# ATOM_-_3x_Attenuverter_Rev5.net
KiCad netlist of a schematic drawn in EAGLE
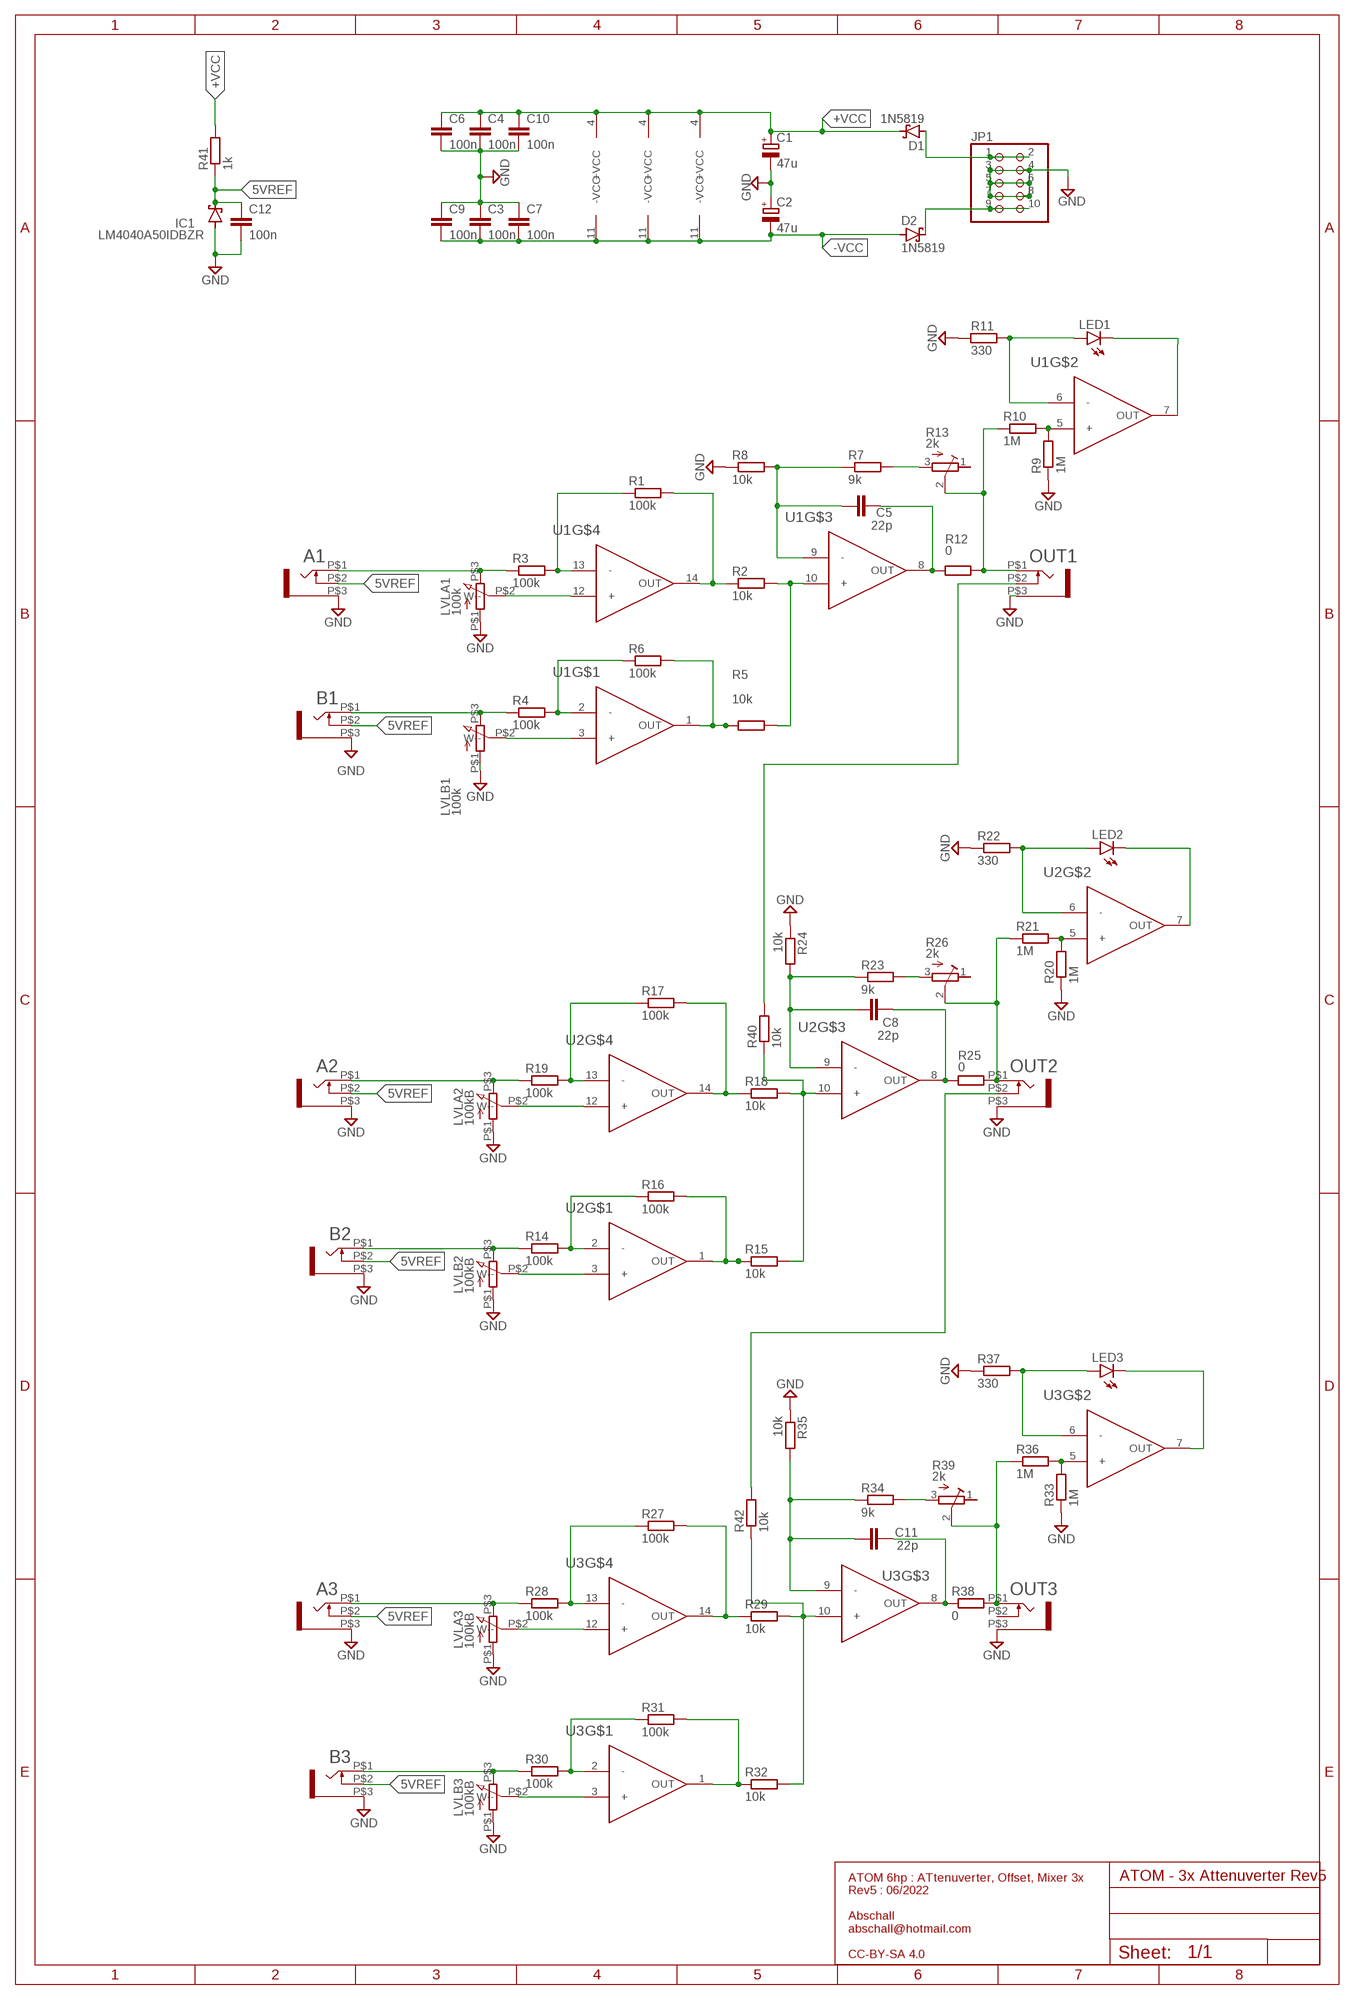
[diagram p0: schematic, sheet 1]

(export (version "E")
  (design (tool "Eeschema 10.0.6"))
  (components
    (comp (ref "A1")
      (value "WQP-PJ301M-12_JACK")
      (footprint "eagle-import:WQP-PJ301M-12_JACK")
      (libsource (lib "eagle-import") (part "WQP-PJ301M-12_JACK"))
    )
    (comp (ref "A2")
      (value "WQP-PJ301M-12_JACK")
      (footprint "eagle-import:WQP-PJ301M-12_JACK")
      (libsource (lib "eagle-import") (part "WQP-PJ301M-12_JACK"))
    )
    (comp (ref "A3")
      (value "WQP-PJ301M-12_JACK")
      (footprint "eagle-import:WQP-PJ301M-12_JACK")
      (libsource (lib "eagle-import") (part "WQP-PJ301M-12_JACK"))
    )
    (comp (ref "B1")
      (value "WQP-PJ301M-12_JACK")
      (footprint "eagle-import:WQP-PJ301M-12_JACK")
      (libsource (lib "eagle-import") (part "WQP-PJ301M-12_JACK"))
    )
    (comp (ref "B2")
      (value "WQP-PJ301M-12_JACK")
      (footprint "eagle-import:WQP-PJ301M-12_JACK")
      (libsource (lib "eagle-import") (part "WQP-PJ301M-12_JACK"))
    )
    (comp (ref "B3")
      (value "WQP-PJ301M-12_JACK")
      (footprint "eagle-import:WQP-PJ301M-12_JACK")
      (libsource (lib "eagle-import") (part "WQP-PJ301M-12_JACK"))
    )
    (comp (ref "C1")
      (value "47u")
      (footprint "eagle-import:PANASONIC_B")
      (libsource (lib "eagle-import") (part "CPOL-EUB"))
    )
    (comp (ref "C2")
      (value "47u")
      (footprint "eagle-import:PANASONIC_B")
      (libsource (lib "eagle-import") (part "CPOL-EUB"))
    )
    (comp (ref "C3")
      (value "100n")
      (footprint "eagle-import:C0805")
      (libsource (lib "eagle-import") (part "C-EUC0805"))
    )
    (comp (ref "C4")
      (value "100n")
      (footprint "eagle-import:C0805")
      (libsource (lib "eagle-import") (part "C-EUC0805"))
    )
    (comp (ref "C5")
      (value "22p")
      (footprint "eagle-import:C0805")
      (libsource (lib "eagle-import") (part "C-EUC0805"))
    )
    (comp (ref "C6")
      (value "100n")
      (footprint "eagle-import:C0805")
      (libsource (lib "eagle-import") (part "C-EUC0805"))
    )
    (comp (ref "C7")
      (value "100n")
      (footprint "eagle-import:C0805")
      (libsource (lib "eagle-import") (part "C-EUC0805"))
    )
    (comp (ref "C8")
      (value "22p")
      (footprint "eagle-import:C0805")
      (libsource (lib "eagle-import") (part "C-EUC0805"))
    )
    (comp (ref "C9")
      (value "100n")
      (footprint "eagle-import:C0805")
      (libsource (lib "eagle-import") (part "C-EUC0805"))
    )
    (comp (ref "C10")
      (value "100n")
      (footprint "eagle-import:C0805")
      (libsource (lib "eagle-import") (part "C-EUC0805"))
    )
    (comp (ref "C11")
      (value "22p")
      (footprint "eagle-import:C0805")
      (libsource (lib "eagle-import") (part "C-EUC0805"))
    )
    (comp (ref "C12")
      (value "100n")
      (footprint "eagle-import:C0805")
      (libsource (lib "eagle-import") (part "C-EUC0805"))
    )
    (comp (ref "D1")
      (value "1N5819")
      (footprint "eagle-import:SOD123")
      (libsource (lib "eagle-import") (part "1N5819"))
    )
    (comp (ref "D2")
      (value "1N5819")
      (footprint "eagle-import:SOD123")
      (libsource (lib "eagle-import") (part "1N5819"))
    )
    (comp (ref "IC1")
      (value "LM4040A50IDBZR")
      (footprint "eagle-import:SOT23")
      (libsource (lib "eagle-import") (part "LM4040"))
    )
    (comp (ref "JP1")
      (value "PINHD-2X5")
      (footprint "eagle-import:2X05")
      (libsource (lib "eagle-import") (part "PINHD-2X5"))
    )
    (comp (ref "LED1")
      (value "LED3MM")
      (footprint "eagle-import:LED3MM")
      (libsource (lib "eagle-import") (part "LED3MM"))
    )
    (comp (ref "LED2")
      (value "LED3MM")
      (footprint "eagle-import:LED3MM")
      (libsource (lib "eagle-import") (part "LED3MM"))
    )
    (comp (ref "LED3")
      (value "LED3MM")
      (footprint "eagle-import:LED3MM")
      (libsource (lib "eagle-import") (part "LED3MM"))
    )
    (comp (ref "LVLA1")
      (value "100k")
      (footprint "eagle-import:ALPHA9MM")
      (libsource (lib "eagle-import") (part "ALPHA9MM"))
    )
    (comp (ref "LVLA2")
      (value "100kB")
      (footprint "eagle-import:ALPHA9MM")
      (libsource (lib "eagle-import") (part "ALPHA9MM"))
    )
    (comp (ref "LVLA3")
      (value "100kB")
      (footprint "eagle-import:ALPHA9MM")
      (libsource (lib "eagle-import") (part "ALPHA9MM"))
    )
    (comp (ref "LVLB1")
      (value "100k")
      (footprint "eagle-import:ALPHA9MM")
      (libsource (lib "eagle-import") (part "ALPHA9MM"))
    )
    (comp (ref "LVLB2")
      (value "100kB")
      (footprint "eagle-import:ALPHA9MM")
      (libsource (lib "eagle-import") (part "ALPHA9MM"))
    )
    (comp (ref "LVLB3")
      (value "100kB")
      (footprint "eagle-import:ALPHA9MM")
      (libsource (lib "eagle-import") (part "ALPHA9MM"))
    )
    (comp (ref "OUT1")
      (value "WQP-PJ301M-12_JACK")
      (footprint "eagle-import:WQP-PJ301M-12_JACK")
      (libsource (lib "eagle-import") (part "WQP-PJ301M-12_JACK"))
    )
    (comp (ref "OUT2")
      (value "WQP-PJ301M-12_JACK")
      (footprint "eagle-import:WQP-PJ301M-12_JACK")
      (libsource (lib "eagle-import") (part "WQP-PJ301M-12_JACK"))
    )
    (comp (ref "OUT3")
      (value "WQP-PJ301M-12_JACK")
      (footprint "eagle-import:WQP-PJ301M-12_JACK")
      (libsource (lib "eagle-import") (part "WQP-PJ301M-12_JACK"))
    )
    (comp (ref "R1")
      (value "100k")
      (footprint "eagle-import:R0805")
      (libsource (lib "eagle-import") (part "R-EU_R0805"))
    )
    (comp (ref "R2")
      (value "10k")
      (footprint "eagle-import:R0805")
      (libsource (lib "eagle-import") (part "R-EU_R0805"))
    )
    (comp (ref "R3")
      (value "100k")
      (footprint "eagle-import:R0805")
      (libsource (lib "eagle-import") (part "R-EU_R0805"))
    )
    (comp (ref "R4")
      (value "100k")
      (footprint "eagle-import:R0805")
      (libsource (lib "eagle-import") (part "R-EU_R0805"))
    )
    (comp (ref "R5")
      (value "10k")
      (footprint "eagle-import:R0805")
      (libsource (lib "eagle-import") (part "R-EU_R0805"))
    )
    (comp (ref "R6")
      (value "100k")
      (footprint "eagle-import:R0805")
      (libsource (lib "eagle-import") (part "R-EU_R0805"))
    )
    (comp (ref "R7")
      (value "9k")
      (footprint "eagle-import:R0805")
      (libsource (lib "eagle-import") (part "R-EU_R0805"))
    )
    (comp (ref "R8")
      (value "10k")
      (footprint "eagle-import:R0805")
      (libsource (lib "eagle-import") (part "R-EU_R0805"))
    )
    (comp (ref "R9")
      (value "1M")
      (footprint "eagle-import:R0805")
      (libsource (lib "eagle-import") (part "R-EU_R0805"))
    )
    (comp (ref "R10")
      (value "1M")
      (footprint "eagle-import:R0805")
      (libsource (lib "eagle-import") (part "R-EU_R0805"))
    )
    (comp (ref "R11")
      (value "330")
      (footprint "eagle-import:R0805")
      (libsource (lib "eagle-import") (part "R-EU_R0805"))
    )
    (comp (ref "R12")
      (value "0")
      (footprint "eagle-import:R0805")
      (libsource (lib "eagle-import") (part "R-EU_R0805"))
    )
    (comp (ref "R13")
      (value "2k")
      (footprint "eagle-import:RTRIM3314J")
      (libsource (lib "eagle-import") (part "R-TRIMM3314J"))
    )
    (comp (ref "R14")
      (value "100k")
      (footprint "eagle-import:R0805")
      (libsource (lib "eagle-import") (part "R-EU_R0805"))
    )
    (comp (ref "R15")
      (value "10k")
      (footprint "eagle-import:R0805")
      (libsource (lib "eagle-import") (part "R-EU_R0805"))
    )
    (comp (ref "R16")
      (value "100k")
      (footprint "eagle-import:R0805")
      (libsource (lib "eagle-import") (part "R-EU_R0805"))
    )
    (comp (ref "R17")
      (value "100k")
      (footprint "eagle-import:R0805")
      (libsource (lib "eagle-import") (part "R-EU_R0805"))
    )
    (comp (ref "R18")
      (value "10k")
      (footprint "eagle-import:R0805")
      (libsource (lib "eagle-import") (part "R-EU_R0805"))
    )
    (comp (ref "R19")
      (value "100k")
      (footprint "eagle-import:R0805")
      (libsource (lib "eagle-import") (part "R-EU_R0805"))
    )
    (comp (ref "R20")
      (value "1M")
      (footprint "eagle-import:R0805")
      (libsource (lib "eagle-import") (part "R-EU_R0805"))
    )
    (comp (ref "R21")
      (value "1M")
      (footprint "eagle-import:R0805")
      (libsource (lib "eagle-import") (part "R-EU_R0805"))
    )
    (comp (ref "R22")
      (value "330")
      (footprint "eagle-import:R0805")
      (libsource (lib "eagle-import") (part "R-EU_R0805"))
    )
    (comp (ref "R23")
      (value "9k")
      (footprint "eagle-import:R0805")
      (libsource (lib "eagle-import") (part "R-EU_R0805"))
    )
    (comp (ref "R24")
      (value "10k")
      (footprint "eagle-import:R0805")
      (libsource (lib "eagle-import") (part "R-EU_R0805"))
    )
    (comp (ref "R25")
      (value "0")
      (footprint "eagle-import:R0805")
      (libsource (lib "eagle-import") (part "R-EU_R0805"))
    )
    (comp (ref "R26")
      (value "2k")
      (footprint "eagle-import:RTRIM3314J")
      (libsource (lib "eagle-import") (part "R-TRIMM3314J"))
    )
    (comp (ref "R27")
      (value "100k")
      (footprint "eagle-import:R0805")
      (libsource (lib "eagle-import") (part "R-EU_R0805"))
    )
    (comp (ref "R28")
      (value "100k")
      (footprint "eagle-import:R0805")
      (libsource (lib "eagle-import") (part "R-EU_R0805"))
    )
    (comp (ref "R29")
      (value "10k")
      (footprint "eagle-import:R0805")
      (libsource (lib "eagle-import") (part "R-EU_R0805"))
    )
    (comp (ref "R30")
      (value "100k")
      (footprint "eagle-import:R0805")
      (libsource (lib "eagle-import") (part "R-EU_R0805"))
    )
    (comp (ref "R31")
      (value "100k")
      (footprint "eagle-import:R0805")
      (libsource (lib "eagle-import") (part "R-EU_R0805"))
    )
    (comp (ref "R32")
      (value "10k")
      (footprint "eagle-import:R0805")
      (libsource (lib "eagle-import") (part "R-EU_R0805"))
    )
    (comp (ref "R33")
      (value "1M")
      (footprint "eagle-import:R0805")
      (libsource (lib "eagle-import") (part "R-EU_R0805"))
    )
    (comp (ref "R34")
      (value "9k")
      (footprint "eagle-import:R0805")
      (libsource (lib "eagle-import") (part "R-EU_R0805"))
    )
    (comp (ref "R35")
      (value "10k")
      (footprint "eagle-import:R0805")
      (libsource (lib "eagle-import") (part "R-EU_R0805"))
    )
    (comp (ref "R36")
      (value "1M")
      (footprint "eagle-import:R0805")
      (libsource (lib "eagle-import") (part "R-EU_R0805"))
    )
    (comp (ref "R37")
      (value "330")
      (footprint "eagle-import:R0805")
      (libsource (lib "eagle-import") (part "R-EU_R0805"))
    )
    (comp (ref "R38")
      (value "0")
      (footprint "eagle-import:R0805")
      (libsource (lib "eagle-import") (part "R-EU_R0805"))
    )
    (comp (ref "R39")
      (value "2k")
      (footprint "eagle-import:RTRIM3314J")
      (libsource (lib "eagle-import") (part "R-TRIMM3314J"))
    )
    (comp (ref "R40")
      (value "10k")
      (footprint "eagle-import:R0805")
      (libsource (lib "eagle-import") (part "R-EU_R0805"))
    )
    (comp (ref "R41")
      (value "1k")
      (footprint "eagle-import:R0805")
      (libsource (lib "eagle-import") (part "R-EU_R0805"))
    )
    (comp (ref "R42")
      (value "10k")
      (footprint "eagle-import:R0805")
      (libsource (lib "eagle-import") (part "R-EU_R0805"))
    )
    (comp (ref "U1")
      (value "TL74H")
      (footprint "eagle-import:SO14")
      (libsource (lib "eagle-import") (part "TL74H"))
    )
    (comp (ref "U2")
      (value "TL74H")
      (footprint "eagle-import:SO14")
      (libsource (lib "eagle-import") (part "TL74H"))
    )
    (comp (ref "U3")
      (value "TL74H")
      (footprint "eagle-import:SO14")
      (libsource (lib "eagle-import") (part "TL74H"))
    )
  )
  (nets
    (net (code "1") (name "+VCC") (class "Default")
      (node (ref "C1") (pin "+") (pinfunction "+_+") (pintype "passive"))
      (node (ref "C10") (pin "1") (pinfunction "1_1") (pintype "passive"))
      (node (ref "C4") (pin "1") (pinfunction "1_1") (pintype "passive"))
      (node (ref "C6") (pin "1") (pinfunction "1_1") (pintype "passive"))
      (node (ref "D1") (pin "C") (pinfunction "C_C") (pintype "passive"))
      (node (ref "R41") (pin "2") (pinfunction "2_2") (pintype "passive"))
      (node (ref "U1") (pin "4") (pinfunction "+VCC_4") (pintype "power_in"))
      (node (ref "U2") (pin "4") (pinfunction "+VCC_4") (pintype "power_in"))
      (node (ref "U3") (pin "4") (pinfunction "+VCC_4") (pintype "power_in"))
    )
    (net (code "2") (name "-VCC") (class "Default")
      (node (ref "C2") (pin "-") (pinfunction "-_-") (pintype "passive"))
      (node (ref "C3") (pin "2") (pinfunction "2_2") (pintype "passive"))
      (node (ref "C7") (pin "2") (pinfunction "2_2") (pintype "passive"))
      (node (ref "C9") (pin "2") (pinfunction "2_2") (pintype "passive"))
      (node (ref "D2") (pin "A") (pinfunction "A_A") (pintype "passive"))
      (node (ref "U1") (pin "11") (pinfunction "-VCC_11") (pintype "power_in"))
      (node (ref "U2") (pin "11") (pinfunction "-VCC_11") (pintype "power_in"))
      (node (ref "U3") (pin "11") (pinfunction "-VCC_11") (pintype "power_in"))
    )
    (net (code "3") (name "5VREF") (class "Default")
      (node (ref "A1") (pin "P$2") (pinfunction "3_P$2") (pintype "passive"))
      (node (ref "A2") (pin "P$2") (pinfunction "3_P$2") (pintype "passive"))
      (node (ref "A3") (pin "P$2") (pinfunction "3_P$2") (pintype "passive"))
      (node (ref "B1") (pin "P$2") (pinfunction "3_P$2") (pintype "passive"))
      (node (ref "B2") (pin "P$2") (pinfunction "3_P$2") (pintype "passive"))
      (node (ref "B3") (pin "P$2") (pinfunction "3_P$2") (pintype "passive"))
      (node (ref "C12") (pin "1") (pinfunction "1_1") (pintype "passive"))
      (node (ref "IC1") (pin "1") (pinfunction "C_1") (pintype "passive"))
      (node (ref "R41") (pin "1") (pinfunction "1_1") (pintype "passive"))
    )
    (net (code "4") (name "GND") (class "Default")
      (node (ref "A1") (pin "P$3") (pinfunction "1_P$3") (pintype "passive"))
      (node (ref "A2") (pin "P$3") (pinfunction "1_P$3") (pintype "passive"))
      (node (ref "A3") (pin "P$3") (pinfunction "1_P$3") (pintype "passive"))
      (node (ref "B1") (pin "P$3") (pinfunction "1_P$3") (pintype "passive"))
      (node (ref "B2") (pin "P$3") (pinfunction "1_P$3") (pintype "passive"))
      (node (ref "B3") (pin "P$3") (pinfunction "1_P$3") (pintype "passive"))
      (node (ref "C1") (pin "-") (pinfunction "-_-") (pintype "passive"))
      (node (ref "C10") (pin "2") (pinfunction "2_2") (pintype "passive"))
      (node (ref "C12") (pin "2") (pinfunction "2_2") (pintype "passive"))
      (node (ref "C2") (pin "+") (pinfunction "+_+") (pintype "passive"))
      (node (ref "C3") (pin "1") (pinfunction "1_1") (pintype "passive"))
      (node (ref "C4") (pin "2") (pinfunction "2_2") (pintype "passive"))
      (node (ref "C6") (pin "2") (pinfunction "2_2") (pintype "passive"))
      (node (ref "C7") (pin "1") (pinfunction "1_1") (pintype "passive"))
      (node (ref "C9") (pin "1") (pinfunction "1_1") (pintype "passive"))
      (node (ref "IC1") (pin "2") (pinfunction "A_2") (pintype "passive"))
      (node (ref "JP1") (pin "3") (pinfunction "3_3") (pintype "passive"))
      (node (ref "JP1") (pin "4") (pinfunction "4_4") (pintype "passive"))
      (node (ref "JP1") (pin "5") (pinfunction "5_5") (pintype "passive"))
      (node (ref "JP1") (pin "6") (pinfunction "6_6") (pintype "passive"))
      (node (ref "JP1") (pin "7") (pinfunction "7_7") (pintype "passive"))
      (node (ref "JP1") (pin "8") (pinfunction "8_8") (pintype "passive"))
      (node (ref "LVLA1") (pin "P$1") (pinfunction "1_P$1") (pintype "passive"))
      (node (ref "LVLA2") (pin "P$1") (pinfunction "1_P$1") (pintype "passive"))
      (node (ref "LVLA3") (pin "P$1") (pinfunction "1_P$1") (pintype "passive"))
      (node (ref "LVLB1") (pin "P$1") (pinfunction "1_P$1") (pintype "passive"))
      (node (ref "LVLB2") (pin "P$1") (pinfunction "1_P$1") (pintype "passive"))
      (node (ref "LVLB3") (pin "P$1") (pinfunction "1_P$1") (pintype "passive"))
      (node (ref "OUT1") (pin "P$3") (pinfunction "1_P$3") (pintype "passive"))
      (node (ref "OUT2") (pin "P$3") (pinfunction "1_P$3") (pintype "passive"))
      (node (ref "OUT3") (pin "P$3") (pinfunction "1_P$3") (pintype "passive"))
      (node (ref "R11") (pin "1") (pinfunction "1_1") (pintype "passive"))
      (node (ref "R20") (pin "1") (pinfunction "1_1") (pintype "passive"))
      (node (ref "R22") (pin "1") (pinfunction "1_1") (pintype "passive"))
      (node (ref "R24") (pin "1") (pinfunction "1_1") (pintype "passive"))
      (node (ref "R33") (pin "1") (pinfunction "1_1") (pintype "passive"))
      (node (ref "R35") (pin "1") (pinfunction "1_1") (pintype "passive"))
      (node (ref "R37") (pin "1") (pinfunction "1_1") (pintype "passive"))
      (node (ref "R8") (pin "1") (pinfunction "1_1") (pintype "passive"))
      (node (ref "R9") (pin "1") (pinfunction "1_1") (pintype "passive"))
    )
    (net (code "5") (name "Net-(A1-2)") (class "Default")
      (node (ref "A1") (pin "P$1") (pinfunction "2_P$1") (pintype "passive"))
      (node (ref "LVLA1") (pin "P$3") (pinfunction "3_P$3") (pintype "passive"))
      (node (ref "R3") (pin "1") (pinfunction "1_1") (pintype "passive"))
    )
    (net (code "6") (name "Net-(A2-2)") (class "Default")
      (node (ref "A2") (pin "P$1") (pinfunction "2_P$1") (pintype "passive"))
      (node (ref "LVLA2") (pin "P$3") (pinfunction "3_P$3") (pintype "passive"))
      (node (ref "R19") (pin "1") (pinfunction "1_1") (pintype "passive"))
    )
    (net (code "7") (name "Net-(A3-2)") (class "Default")
      (node (ref "A3") (pin "P$1") (pinfunction "2_P$1") (pintype "passive"))
      (node (ref "LVLA3") (pin "P$3") (pinfunction "3_P$3") (pintype "passive"))
      (node (ref "R28") (pin "1") (pinfunction "1_1") (pintype "passive"))
    )
    (net (code "8") (name "Net-(B1-2)") (class "Default")
      (node (ref "B1") (pin "P$1") (pinfunction "2_P$1") (pintype "passive"))
      (node (ref "LVLB1") (pin "P$3") (pinfunction "3_P$3") (pintype "passive"))
      (node (ref "R4") (pin "1") (pinfunction "1_1") (pintype "passive"))
    )
    (net (code "9") (name "Net-(B2-2)") (class "Default")
      (node (ref "B2") (pin "P$1") (pinfunction "2_P$1") (pintype "passive"))
      (node (ref "LVLB2") (pin "P$3") (pinfunction "3_P$3") (pintype "passive"))
      (node (ref "R14") (pin "1") (pinfunction "1_1") (pintype "passive"))
    )
    (net (code "10") (name "Net-(B3-2)") (class "Default")
      (node (ref "B3") (pin "P$1") (pinfunction "2_P$1") (pintype "passive"))
      (node (ref "LVLB3") (pin "P$3") (pinfunction "3_P$3") (pintype "passive"))
      (node (ref "R30") (pin "1") (pinfunction "1_1") (pintype "passive"))
    )
    (net (code "11") (name "Net-(D1-PadA)") (class "Default")
      (node (ref "D1") (pin "A") (pinfunction "A_A") (pintype "passive"))
      (node (ref "JP1") (pin "1") (pinfunction "1_1") (pintype "passive"))
      (node (ref "JP1") (pin "2") (pinfunction "2_2") (pintype "passive"))
    )
    (net (code "12") (name "Net-(D2-PadC)") (class "Default")
      (node (ref "D2") (pin "C") (pinfunction "C_C") (pintype "passive"))
      (node (ref "JP1") (pin "10") (pinfunction "10_10") (pintype "passive"))
      (node (ref "JP1") (pin "9") (pinfunction "9_9") (pintype "passive"))
    )
    (net (code "13") (name "Net-(LED1-C)") (class "Default")
      (node (ref "LED1") (pin "K") (pinfunction "C_K") (pintype "passive"))
      (node (ref "U1") (pin "7") (pinfunction "OUT_7") (pintype "output"))
    )
    (net (code "14") (name "Net-(LED2-C)") (class "Default")
      (node (ref "LED2") (pin "K") (pinfunction "C_K") (pintype "passive"))
      (node (ref "U2") (pin "7") (pinfunction "OUT_7") (pintype "output"))
    )
    (net (code "15") (name "Net-(LED3-C)") (class "Default")
      (node (ref "LED3") (pin "K") (pinfunction "C_K") (pintype "passive"))
      (node (ref "U3") (pin "7") (pinfunction "OUT_7") (pintype "output"))
    )
    (net (code "16") (name "Net-(LVLA1-W--)") (class "Default")
      (node (ref "LVLA1") (pin "P$2") (pinfunction "W--_P$2") (pintype "passive"))
      (node (ref "U1") (pin "12") (pinfunction "+_12") (pintype "input"))
    )
    (net (code "17") (name "Net-(LVLA2-W--)") (class "Default")
      (node (ref "LVLA2") (pin "P$2") (pinfunction "W--_P$2") (pintype "passive"))
      (node (ref "U2") (pin "12") (pinfunction "+_12") (pintype "input"))
    )
    (net (code "18") (name "Net-(LVLA3-W--)") (class "Default")
      (node (ref "LVLA3") (pin "P$2") (pinfunction "W--_P$2") (pintype "passive"))
      (node (ref "U3") (pin "12") (pinfunction "+_12") (pintype "input"))
    )
    (net (code "19") (name "Net-(LVLB1-W--)") (class "Default")
      (node (ref "LVLB1") (pin "P$2") (pinfunction "W--_P$2") (pintype "passive"))
      (node (ref "U1") (pin "3") (pinfunction "+_3") (pintype "input"))
    )
    (net (code "20") (name "Net-(LVLB2-W--)") (class "Default")
      (node (ref "LVLB2") (pin "P$2") (pinfunction "W--_P$2") (pintype "passive"))
      (node (ref "U2") (pin "3") (pinfunction "+_3") (pintype "input"))
    )
    (net (code "21") (name "Net-(LVLB3-W--)") (class "Default")
      (node (ref "LVLB3") (pin "P$2") (pinfunction "W--_P$2") (pintype "passive"))
      (node (ref "U3") (pin "3") (pinfunction "+_3") (pintype "input"))
    )
    (net (code "22") (name "Net-(OUT1-2)") (class "Default")
      (node (ref "OUT1") (pin "P$1") (pinfunction "2_P$1") (pintype "passive"))
      (node (ref "R10") (pin "1") (pinfunction "1_1") (pintype "passive"))
      (node (ref "R12") (pin "2") (pinfunction "2_2") (pintype "passive"))
      (node (ref "R13") (pin "2") (pinfunction "S_2") (pintype "passive"))
    )
    (net (code "23") (name "Net-(OUT1-3)") (class "Default")
      (node (ref "OUT1") (pin "P$2") (pinfunction "3_P$2") (pintype "passive"))
      (node (ref "R40") (pin "2") (pinfunction "2_2") (pintype "passive"))
    )
    (net (code "24") (name "Net-(OUT2-2)") (class "Default")
      (node (ref "OUT2") (pin "P$1") (pinfunction "2_P$1") (pintype "passive"))
      (node (ref "R21") (pin "1") (pinfunction "1_1") (pintype "passive"))
      (node (ref "R25") (pin "2") (pinfunction "2_2") (pintype "passive"))
      (node (ref "R26") (pin "2") (pinfunction "S_2") (pintype "passive"))
    )
    (net (code "25") (name "Net-(OUT2-3)") (class "Default")
      (node (ref "OUT2") (pin "P$2") (pinfunction "3_P$2") (pintype "passive"))
      (node (ref "R42") (pin "2") (pinfunction "2_2") (pintype "passive"))
    )
    (net (code "26") (name "Net-(OUT3-2)") (class "Default")
      (node (ref "OUT3") (pin "P$1") (pinfunction "2_P$1") (pintype "passive"))
      (node (ref "R36") (pin "1") (pinfunction "1_1") (pintype "passive"))
      (node (ref "R38") (pin "2") (pinfunction "2_2") (pintype "passive"))
      (node (ref "R39") (pin "2") (pinfunction "S_2") (pintype "passive"))
    )
    (net (code "27") (name "Net-(R13-A)") (class "Default")
      (node (ref "R13") (pin "3") (pinfunction "A_3") (pintype "passive"))
      (node (ref "R7") (pin "2") (pinfunction "2_2") (pintype "passive"))
    )
    (net (code "28") (name "Net-(R26-A)") (class "Default")
      (node (ref "R23") (pin "2") (pinfunction "2_2") (pintype "passive"))
      (node (ref "R26") (pin "3") (pinfunction "A_3") (pintype "passive"))
    )
    (net (code "29") (name "Net-(R39-A)") (class "Default")
      (node (ref "R34") (pin "2") (pinfunction "2_2") (pintype "passive"))
      (node (ref "R39") (pin "3") (pinfunction "A_3") (pintype "passive"))
    )
    (net (code "30") (name "Net-(U1A--)") (class "Default")
      (node (ref "R4") (pin "2") (pinfunction "2_2") (pintype "passive"))
      (node (ref "R6") (pin "1") (pinfunction "1_1") (pintype "passive"))
      (node (ref "U1") (pin "2") (pinfunction "-_2") (pintype "input"))
    )
    (net (code "31") (name "Net-(U1A-OUT)") (class "Default")
      (node (ref "R5") (pin "1") (pinfunction "1_1") (pintype "passive"))
      (node (ref "R6") (pin "2") (pinfunction "2_2") (pintype "passive"))
      (node (ref "U1") (pin "1") (pinfunction "OUT_1") (pintype "output"))
    )
    (net (code "32") (name "Net-(U1B-+)") (class "Default")
      (node (ref "R10") (pin "2") (pinfunction "2_2") (pintype "passive"))
      (node (ref "R9") (pin "2") (pinfunction "2_2") (pintype "passive"))
      (node (ref "U1") (pin "5") (pinfunction "+_5") (pintype "input"))
    )
    (net (code "33") (name "Net-(U1B--)") (class "Default")
      (node (ref "LED1") (pin "A") (pinfunction "A_A") (pintype "passive"))
      (node (ref "R11") (pin "2") (pinfunction "2_2") (pintype "passive"))
      (node (ref "U1") (pin "6") (pinfunction "-_6") (pintype "input"))
    )
    (net (code "34") (name "Net-(U1C-+)") (class "Default")
      (node (ref "R2") (pin "2") (pinfunction "2_2") (pintype "passive"))
      (node (ref "R5") (pin "2") (pinfunction "2_2") (pintype "passive"))
      (node (ref "U1") (pin "10") (pinfunction "+_10") (pintype "input"))
    )
    (net (code "35") (name "Net-(U1C--)") (class "Default")
      (node (ref "C5") (pin "1") (pinfunction "1_1") (pintype "passive"))
      (node (ref "R7") (pin "1") (pinfunction "1_1") (pintype "passive"))
      (node (ref "R8") (pin "2") (pinfunction "2_2") (pintype "passive"))
      (node (ref "U1") (pin "9") (pinfunction "-_9") (pintype "input"))
    )
    (net (code "36") (name "Net-(U1C-OUT)") (class "Default")
      (node (ref "C5") (pin "2") (pinfunction "2_2") (pintype "passive"))
      (node (ref "R12") (pin "1") (pinfunction "1_1") (pintype "passive"))
      (node (ref "U1") (pin "8") (pinfunction "OUT_8") (pintype "output"))
    )
    (net (code "37") (name "Net-(U1D--)") (class "Default")
      (node (ref "R1") (pin "1") (pinfunction "1_1") (pintype "passive"))
      (node (ref "R3") (pin "2") (pinfunction "2_2") (pintype "passive"))
      (node (ref "U1") (pin "13") (pinfunction "-_13") (pintype "input"))
    )
    (net (code "38") (name "Net-(U1D-OUT)") (class "Default")
      (node (ref "R1") (pin "2") (pinfunction "2_2") (pintype "passive"))
      (node (ref "R2") (pin "1") (pinfunction "1_1") (pintype "passive"))
      (node (ref "U1") (pin "14") (pinfunction "OUT_14") (pintype "output"))
    )
    (net (code "39") (name "Net-(U2A--)") (class "Default")
      (node (ref "R14") (pin "2") (pinfunction "2_2") (pintype "passive"))
      (node (ref "R16") (pin "1") (pinfunction "1_1") (pintype "passive"))
      (node (ref "U2") (pin "2") (pinfunction "-_2") (pintype "input"))
    )
    (net (code "40") (name "Net-(U2A-OUT)") (class "Default")
      (node (ref "R15") (pin "1") (pinfunction "1_1") (pintype "passive"))
      (node (ref "R16") (pin "2") (pinfunction "2_2") (pintype "passive"))
      (node (ref "U2") (pin "1") (pinfunction "OUT_1") (pintype "output"))
    )
    (net (code "41") (name "Net-(U2B-+)") (class "Default")
      (node (ref "R20") (pin "2") (pinfunction "2_2") (pintype "passive"))
      (node (ref "R21") (pin "2") (pinfunction "2_2") (pintype "passive"))
      (node (ref "U2") (pin "5") (pinfunction "+_5") (pintype "input"))
    )
    (net (code "42") (name "Net-(U2B--)") (class "Default")
      (node (ref "LED2") (pin "A") (pinfunction "A_A") (pintype "passive"))
      (node (ref "R22") (pin "2") (pinfunction "2_2") (pintype "passive"))
      (node (ref "U2") (pin "6") (pinfunction "-_6") (pintype "input"))
    )
    (net (code "43") (name "Net-(U2C-+)") (class "Default")
      (node (ref "R15") (pin "2") (pinfunction "2_2") (pintype "passive"))
      (node (ref "R18") (pin "2") (pinfunction "2_2") (pintype "passive"))
      (node (ref "R40") (pin "1") (pinfunction "1_1") (pintype "passive"))
      (node (ref "U2") (pin "10") (pinfunction "+_10") (pintype "input"))
    )
    (net (code "44") (name "Net-(U2C--)") (class "Default")
      (node (ref "C8") (pin "1") (pinfunction "1_1") (pintype "passive"))
      (node (ref "R23") (pin "1") (pinfunction "1_1") (pintype "passive"))
      (node (ref "R24") (pin "2") (pinfunction "2_2") (pintype "passive"))
      (node (ref "U2") (pin "9") (pinfunction "-_9") (pintype "input"))
    )
    (net (code "45") (name "Net-(U2C-OUT)") (class "Default")
      (node (ref "C8") (pin "2") (pinfunction "2_2") (pintype "passive"))
      (node (ref "R25") (pin "1") (pinfunction "1_1") (pintype "passive"))
      (node (ref "U2") (pin "8") (pinfunction "OUT_8") (pintype "output"))
    )
    (net (code "46") (name "Net-(U2D--)") (class "Default")
      (node (ref "R17") (pin "1") (pinfunction "1_1") (pintype "passive"))
      (node (ref "R19") (pin "2") (pinfunction "2_2") (pintype "passive"))
      (node (ref "U2") (pin "13") (pinfunction "-_13") (pintype "input"))
    )
    (net (code "47") (name "Net-(U2D-OUT)") (class "Default")
      (node (ref "R17") (pin "2") (pinfunction "2_2") (pintype "passive"))
      (node (ref "R18") (pin "1") (pinfunction "1_1") (pintype "passive"))
      (node (ref "U2") (pin "14") (pinfunction "OUT_14") (pintype "output"))
    )
    (net (code "48") (name "Net-(U3A--)") (class "Default")
      (node (ref "R30") (pin "2") (pinfunction "2_2") (pintype "passive"))
      (node (ref "R31") (pin "1") (pinfunction "1_1") (pintype "passive"))
      (node (ref "U3") (pin "2") (pinfunction "-_2") (pintype "input"))
    )
    (net (code "49") (name "Net-(U3A-OUT)") (class "Default")
      (node (ref "R31") (pin "2") (pinfunction "2_2") (pintype "passive"))
      (node (ref "R32") (pin "1") (pinfunction "1_1") (pintype "passive"))
      (node (ref "U3") (pin "1") (pinfunction "OUT_1") (pintype "output"))
    )
    (net (code "50") (name "Net-(U3B-+)") (class "Default")
      (node (ref "R33") (pin "2") (pinfunction "2_2") (pintype "passive"))
      (node (ref "R36") (pin "2") (pinfunction "2_2") (pintype "passive"))
      (node (ref "U3") (pin "5") (pinfunction "+_5") (pintype "input"))
    )
    (net (code "51") (name "Net-(U3B--)") (class "Default")
      (node (ref "LED3") (pin "A") (pinfunction "A_A") (pintype "passive"))
      (node (ref "R37") (pin "2") (pinfunction "2_2") (pintype "passive"))
      (node (ref "U3") (pin "6") (pinfunction "-_6") (pintype "input"))
    )
    (net (code "52") (name "Net-(U3C-+)") (class "Default")
      (node (ref "R29") (pin "2") (pinfunction "2_2") (pintype "passive"))
      (node (ref "R32") (pin "2") (pinfunction "2_2") (pintype "passive"))
      (node (ref "R42") (pin "1") (pinfunction "1_1") (pintype "passive"))
      (node (ref "U3") (pin "10") (pinfunction "+_10") (pintype "input"))
    )
    (net (code "53") (name "Net-(U3C--)") (class "Default")
      (node (ref "C11") (pin "1") (pinfunction "1_1") (pintype "passive"))
      (node (ref "R34") (pin "1") (pinfunction "1_1") (pintype "passive"))
      (node (ref "R35") (pin "2") (pinfunction "2_2") (pintype "passive"))
      (node (ref "U3") (pin "9") (pinfunction "-_9") (pintype "input"))
    )
    (net (code "54") (name "Net-(U3C-OUT)") (class "Default")
      (node (ref "C11") (pin "2") (pinfunction "2_2") (pintype "passive"))
      (node (ref "R38") (pin "1") (pinfunction "1_1") (pintype "passive"))
      (node (ref "U3") (pin "8") (pinfunction "OUT_8") (pintype "output"))
    )
    (net (code "55") (name "Net-(U3D--)") (class "Default")
      (node (ref "R27") (pin "1") (pinfunction "1_1") (pintype "passive"))
      (node (ref "R28") (pin "2") (pinfunction "2_2") (pintype "passive"))
      (node (ref "U3") (pin "13") (pinfunction "-_13") (pintype "input"))
    )
    (net (code "56") (name "Net-(U3D-OUT)") (class "Default")
      (node (ref "R27") (pin "2") (pinfunction "2_2") (pintype "passive"))
      (node (ref "R29") (pin "1") (pinfunction "1_1") (pintype "passive"))
      (node (ref "U3") (pin "14") (pinfunction "OUT_14") (pintype "output"))
    )
    (net (code "57") (name "unconnected-(OUT3-3-PadP$2)") (class "Default")
      (node (ref "OUT3") (pin "P$2") (pinfunction "3_P$2") (pintype "passive"))
    )
    (net (code "58") (name "unconnected-(R13-E-Pad1)") (class "Default")
      (node (ref "R13") (pin "1") (pinfunction "E_1") (pintype "passive"))
    )
    (net (code "59") (name "unconnected-(R26-E-Pad1)") (class "Default")
      (node (ref "R26") (pin "1") (pinfunction "E_1") (pintype "passive"))
    )
    (net (code "60") (name "unconnected-(R39-E-Pad1)") (class "Default")
      (node (ref "R39") (pin "1") (pinfunction "E_1") (pintype "passive"))
    )
  )
)
